# sd_card.net
KiCad netlist of a schematic drawn in Altium Designer
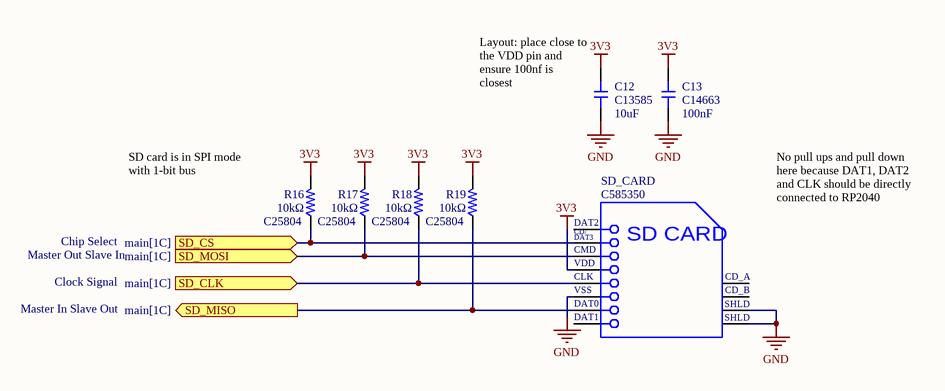
[diagram p0: sd_card.SchDoc]

(export (version "E")
  (design (tool "Eeschema 10.0.6"))
  (components
    (comp (ref "C12")
      (value "CL31A106KBHNNNE")
      (footprint "CAP-1206")
      (description "Capacitor, Ceramic (MLCC), 10uF, ±10%, 50V, X5R, ±10%, SMD 1206")
      (fields
        (field (name "CAPACITANCE") "10uF")
        (field (name "JLCPCB BASIC PART") "Yes")
        (field (name "TOLERANCE") "±10%")
        (field (name "JLCPCB PART") "C13585")
      )
      (libsource (lib "James Cook University") (part "GRM21BR61H106KE43L"))
    )
    (comp (ref "C13")
      (value "CC0603KRX7R9BB104")
      (footprint "CAP-0603")
      (description "Capacitor, Ceramic (MLCC), 100nF, ±10%, 50V, X7R, ±10%, SMD 0603")
      (fields
        (field (name "CAPACITANCE") "100nF")
        (field (name "JLCPCB PART NUMBER") "C14663")
        (field (name "MANUFACTURER") "YAGEO")
        (field (name "JLCPCB PART") "C14663")
      )
      (libsource (lib "James Cook University") (part "GRM21BR61H106KE43L"))
    )
    (comp (ref "R16")
      (value "0603WAF1002T5E")
      (footprint "RES-0603")
      (description "Resistor, 10kΩ, ±1%, 100mW, 75V, ±100ppm/℃, -55℃~+155℃, SMD 0603")
      (fields
        (field (name "RESISTANCE") "10kΩ")
        (field (name "MANUFACTURER") "Uniroyal")
        (field (name "TOLERANCE") "±1%")
        (field (name "JLCPCB PART") "C25804")
      )
      (libsource (lib "James Cook University") (part "1206W4F7500T5E"))
    )
    (comp (ref "R17")
      (value "0603WAF1002T5E")
      (footprint "RES-0603")
      (description "Resistor, 10kΩ, ±1%, 100mW, 75V, ±100ppm/℃, -55℃~+155℃, SMD 0603")
      (fields
        (field (name "RESISTANCE") "10kΩ")
        (field (name "MANUFACTURER") "Uniroyal")
        (field (name "TOLERANCE") "±1%")
        (field (name "JLCPCB PART") "C25804")
      )
      (libsource (lib "James Cook University") (part "1206W4F7500T5E"))
    )
    (comp (ref "R18")
      (value "0603WAF1002T5E")
      (footprint "RES-0603")
      (description "Resistor, 10kΩ, ±1%, 100mW, 75V, ±100ppm/℃, -55℃~+155℃, SMD 0603")
      (fields
        (field (name "RESISTANCE") "10kΩ")
        (field (name "MANUFACTURER") "Uniroyal")
        (field (name "TOLERANCE") "±1%")
        (field (name "JLCPCB PART") "C25804")
      )
      (libsource (lib "James Cook University") (part "1206W4F7500T5E"))
    )
    (comp (ref "R19")
      (value "0603WAF1002T5E")
      (footprint "RES-0603")
      (description "Resistor, 10kΩ, ±1%, 100mW, 75V, ±100ppm/℃, -55℃~+155℃, SMD 0603")
      (fields
        (field (name "RESISTANCE") "10kΩ")
        (field (name "MANUFACTURER") "Uniroyal")
        (field (name "TOLERANCE") "±1%")
        (field (name "JLCPCB PART") "C25804")
      )
      (libsource (lib "James Cook University") (part "1206W4F7500T5E"))
    )
    (comp (ref "SD_CARD")
      (value "104031-0811")
      (footprint "MOLX-104031-0811_V")
      (description "Micro SD Card, RA, -25 to 85 degC, 8-Pin SMD, RoHS, Tape and Reel")
      (fields (field (name "MANUFACTURER") "Molex") (field (name "JLCPCB PART") "C585350"))
      (libsource (lib "Altium Content Vault") (part "CN-SD-8-2SW-2S"))
    )
  )
  (nets
    (net (code "1") (name "/SD_CLK") (class "Default")
      (node (ref "R18") (pin "1") (pinfunction "1_1") (pintype "passive"))
      (node (ref "SD_CARD") (pin "5") (pinfunction "CLK_5") (pintype "passive"))
    )
    (net (code "2") (name "/SD_CS") (class "Default")
      (node (ref "R16") (pin "1") (pinfunction "1_1") (pintype "passive"))
      (node (ref "SD_CARD") (pin "2") (pinfunction "CMD_2") (pintype "passive"))
    )
    (net (code "3") (name "/SD_MISO") (class "Default")
      (node (ref "R19") (pin "1") (pinfunction "1_1") (pintype "passive"))
      (node (ref "SD_CARD") (pin "7") (pinfunction "DAT0_7") (pintype "passive"))
    )
    (net (code "4") (name "/SD_MOSI") (class "Default")
      (node (ref "R17") (pin "1") (pinfunction "1_1") (pintype "passive"))
      (node (ref "SD_CARD") (pin "3") (pinfunction "VSS1_3") (pintype "passive"))
    )
    (net (code "5") (name "3V3") (class "Default")
      (node (ref "C12") (pin "2") (pinfunction "2_2") (pintype "passive"))
      (node (ref "C13") (pin "2") (pinfunction "2_2") (pintype "passive"))
      (node (ref "R16") (pin "2") (pinfunction "2_2") (pintype "passive"))
      (node (ref "R17") (pin "2") (pinfunction "2_2") (pintype "passive"))
      (node (ref "R18") (pin "2") (pinfunction "2_2") (pintype "passive"))
      (node (ref "R19") (pin "2") (pinfunction "2_2") (pintype "passive"))
      (node (ref "SD_CARD") (pin "4") (pinfunction "VDD_4") (pintype "passive"))
    )
    (net (code "6") (name "GND") (class "Default")
      (node (ref "C12") (pin "1") (pinfunction "1_1") (pintype "passive"))
      (node (ref "C13") (pin "1") (pinfunction "1_1") (pintype "passive"))
      (node (ref "SD_CARD") (pin "11") (pinfunction "SHLD1_11") (pintype "passive"))
      (node (ref "SD_CARD") (pin "12") (pinfunction "SHLD2_12") (pintype "passive"))
      (node (ref "SD_CARD") (pin "6") (pinfunction "VSS2_6") (pintype "passive"))
    )
    (net (code "7") (name "unconnected-(SD_CARD-CD_A-Pad9)") (class "Default")
      (node (ref "SD_CARD") (pin "9") (pinfunction "CD_A_9") (pintype "passive"))
    )
    (net (code "8") (name "unconnected-(SD_CARD-CD_B-Pad10)") (class "Default")
      (node (ref "SD_CARD") (pin "10") (pinfunction "CD_B_10") (pintype "passive"))
    )
    (net (code "9") (name "unconnected-(SD_CARD-CD{slash}DAT3-Pad1)") (class "Default")
      (node (ref "SD_CARD") (pin "1") (pinfunction "CD/DAT3_1") (pintype "passive"))
    )
    (net (code "10") (name "unconnected-(SD_CARD-DAT1-Pad8)") (class "Default")
      (node (ref "SD_CARD") (pin "8") (pinfunction "DAT1_8") (pintype "passive"))
    )
  )
)
